# sheet1.net
KiCad netlist of a schematic drawn in Altium Designer
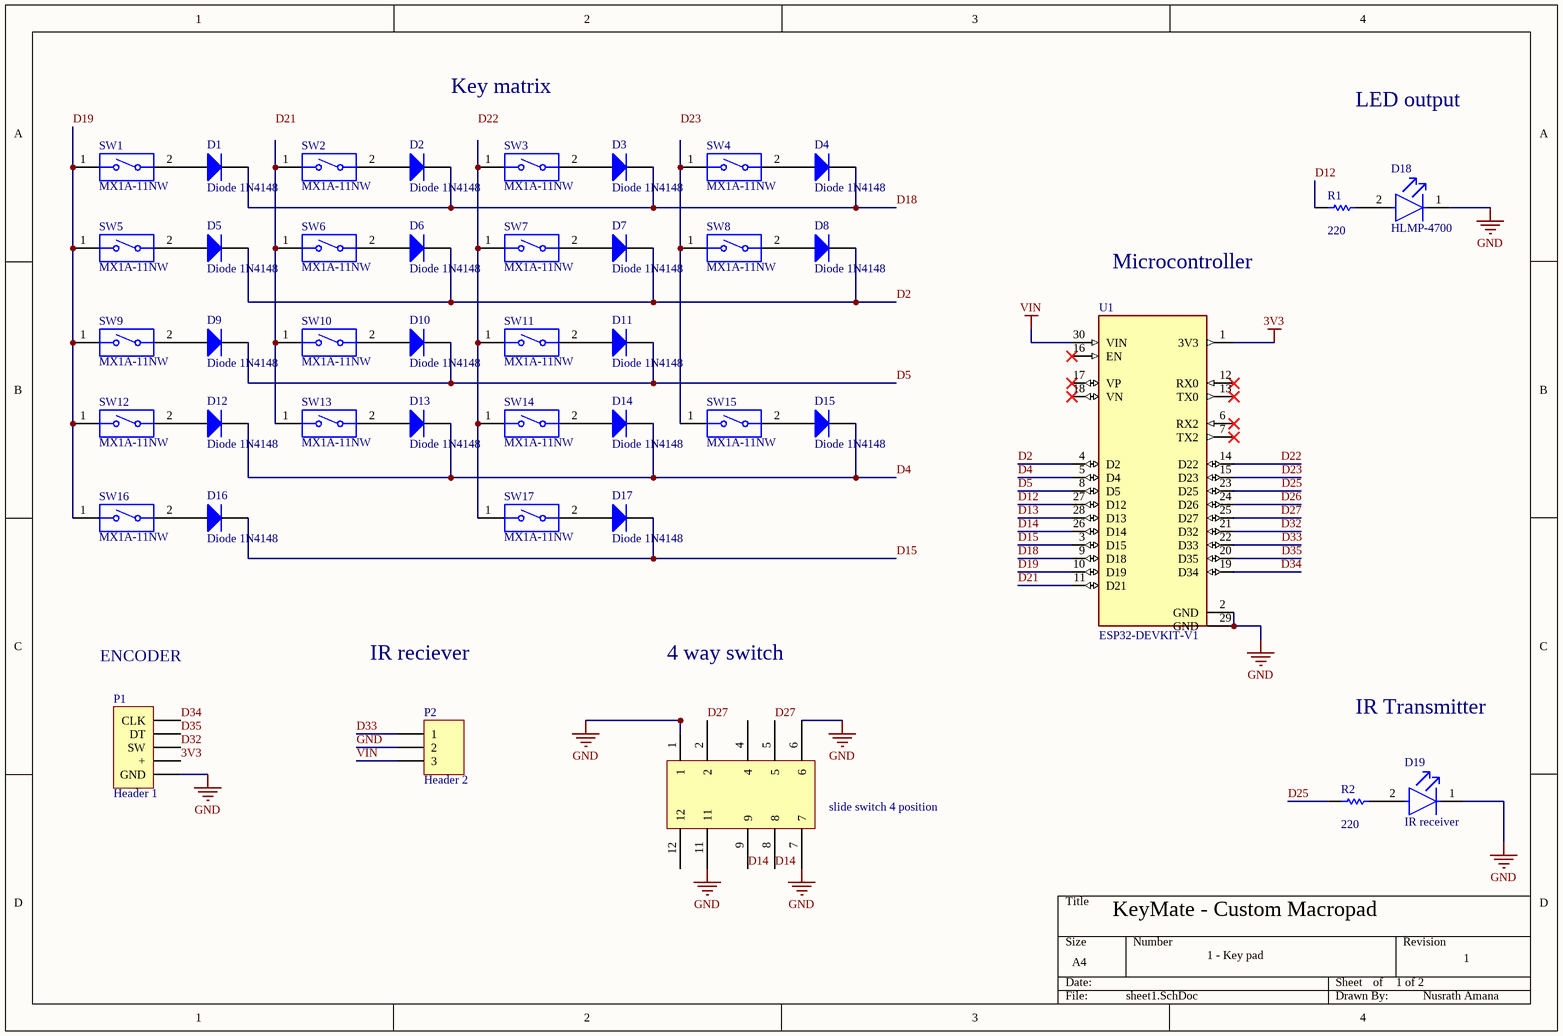
[diagram p0: sheet1.SchDoc]

(export (version "E")
  (design (tool "Eeschema 10.0.6"))
  (components
    (comp (ref "*1")
      (value "slide switch 4 position")
      (footprint "SWSLIDT_DP4T_S_20X8")
      (libsource (lib "switch") (part "slide switch 4 position"))
    )
    (comp (ref "D1")
      (value "Diode 1N4148")
      (footprint "DO-35")
      (description "High Conductance Fast Diode")
      (fields (field (name "PUBLISHER") "Altium Limited"))
      (libsource (lib "Miscellaneous Devices") (part "Diode 1N4148"))
    )
    (comp (ref "D2")
      (value "Diode 1N4148")
      (footprint "DO-35")
      (description "High Conductance Fast Diode")
      (fields (field (name "PUBLISHER") "Altium Limited"))
      (libsource (lib "Miscellaneous Devices") (part "Diode 1N4148"))
    )
    (comp (ref "D3")
      (value "Diode 1N4148")
      (footprint "DO-35")
      (description "High Conductance Fast Diode")
      (fields (field (name "PUBLISHER") "Altium Limited"))
      (libsource (lib "Miscellaneous Devices") (part "Diode 1N4148"))
    )
    (comp (ref "D4")
      (value "Diode 1N4148")
      (footprint "DO-35")
      (description "High Conductance Fast Diode")
      (fields (field (name "PUBLISHER") "Altium Limited"))
      (libsource (lib "Miscellaneous Devices") (part "Diode 1N4148"))
    )
    (comp (ref "D5")
      (value "Diode 1N4148")
      (footprint "DO-35")
      (description "High Conductance Fast Diode")
      (fields (field (name "PUBLISHER") "Altium Limited"))
      (libsource (lib "Miscellaneous Devices") (part "Diode 1N4148"))
    )
    (comp (ref "D6")
      (value "Diode 1N4148")
      (footprint "DO-35")
      (description "High Conductance Fast Diode")
      (fields (field (name "PUBLISHER") "Altium Limited"))
      (libsource (lib "Miscellaneous Devices") (part "Diode 1N4148"))
    )
    (comp (ref "D7")
      (value "Diode 1N4148")
      (footprint "DO-35")
      (description "High Conductance Fast Diode")
      (fields (field (name "PUBLISHER") "Altium Limited"))
      (libsource (lib "Miscellaneous Devices") (part "Diode 1N4148"))
    )
    (comp (ref "D8")
      (value "Diode 1N4148")
      (footprint "DO-35")
      (description "High Conductance Fast Diode")
      (fields (field (name "PUBLISHER") "Altium Limited"))
      (libsource (lib "Miscellaneous Devices") (part "Diode 1N4148"))
    )
    (comp (ref "D9")
      (value "Diode 1N4148")
      (footprint "DO-35")
      (description "High Conductance Fast Diode")
      (fields (field (name "PUBLISHER") "Altium Limited"))
      (libsource (lib "Miscellaneous Devices") (part "Diode 1N4148"))
    )
    (comp (ref "D10")
      (value "Diode 1N4148")
      (footprint "DO-35")
      (description "High Conductance Fast Diode")
      (fields (field (name "PUBLISHER") "Altium Limited"))
      (libsource (lib "Miscellaneous Devices") (part "Diode 1N4148"))
    )
    (comp (ref "D11")
      (value "Diode 1N4148")
      (footprint "DO-35")
      (description "High Conductance Fast Diode")
      (fields (field (name "PUBLISHER") "Altium Limited"))
      (libsource (lib "Miscellaneous Devices") (part "Diode 1N4148"))
    )
    (comp (ref "D12")
      (value "Diode 1N4148")
      (footprint "DO-35")
      (description "High Conductance Fast Diode")
      (fields (field (name "PUBLISHER") "Altium Limited"))
      (libsource (lib "Miscellaneous Devices") (part "Diode 1N4148"))
    )
    (comp (ref "D13")
      (value "Diode 1N4148")
      (footprint "DO-35")
      (description "High Conductance Fast Diode")
      (fields (field (name "PUBLISHER") "Altium Limited"))
      (libsource (lib "Miscellaneous Devices") (part "Diode 1N4148"))
    )
    (comp (ref "D14")
      (value "Diode 1N4148")
      (footprint "DO-35")
      (description "High Conductance Fast Diode")
      (fields (field (name "PUBLISHER") "Altium Limited"))
      (libsource (lib "Miscellaneous Devices") (part "Diode 1N4148"))
    )
    (comp (ref "D15")
      (value "Diode 1N4148")
      (footprint "DO-35")
      (description "High Conductance Fast Diode")
      (fields (field (name "PUBLISHER") "Altium Limited"))
      (libsource (lib "Miscellaneous Devices") (part "Diode 1N4148"))
    )
    (comp (ref "D16")
      (value "Diode 1N4148")
      (footprint "DO-35")
      (description "High Conductance Fast Diode")
      (fields (field (name "PUBLISHER") "Altium Limited"))
      (libsource (lib "Miscellaneous Devices") (part "Diode 1N4148"))
    )
    (comp (ref "D17")
      (value "Diode 1N4148")
      (footprint "DO-35")
      (description "High Conductance Fast Diode")
      (fields (field (name "PUBLISHER") "Altium Limited"))
      (libsource (lib "Miscellaneous Devices") (part "Diode 1N4148"))
    )
    (comp (ref "D18")
      (value "HLMP-4700")
      (footprint "FP-HLMP-4700-MFG")
      (description "LED RED DIFFUSED T-1 3/4 T/H")
      (fields
        (field (name "OCTOPART") "https://octopart.com/hlmp-4700-broadcom-71130526")
        (field (name "MANUFACTURER") "Broadcom")
      )
      (libsource (lib "Altium Content Vault") (part "8706943c75ba83719d021d2fdc84c58"))
    )
    (comp (ref "D19")
      (value "IR receiver")
      (footprint "FP-SFH_4550-MFG")
      (description "EMITTER IR 860NM 100MA RADIAL")
      (fields
        (field (name "MANUFACTURER PART NUMBER") "SFH 4550")
        (field (name "OCTOPART") "https://octopart.com/sfh+4550-osram+opto-55410894")
      )
      (libsource (lib "Altium Content Vault") (part "75a0115997dd6a71327e26aab64f6f8"))
    )
    (comp (ref "P1")
      (value "Header 1")
      (footprint "HDR1X5")
      (description "Header, 5-Pin")
      (fields (field (name "PUBLISHER") "Altium Limited"))
      (libsource (lib "Miscellaneous Connectors") (part "Header 5"))
    )
    (comp (ref "P2")
      (value "Header 2")
      (footprint "HDR1X3")
      (description "Header, 3-Pin")
      (fields (field (name "PUBLISHER") "Altium Limited"))
      (libsource (lib "Miscellaneous Connectors") (part "Header 3"))
    )
    (comp (ref "R1")
      (value "220")
      (footprint "AXIAL-0.3")
      (description "Resistor")
      (fields (field (name "Comment") "Res1") (field (name "PUBLISHER") "Altium Limited"))
      (libsource (lib "Miscellaneous Devices") (part "Res1"))
    )
    (comp (ref "R2")
      (value "220")
      (footprint "AXIAL-0.3")
      (description "Resistor")
      (fields (field (name "Comment") "Res1") (field (name "PUBLISHER") "Altium Limited"))
      (libsource (lib "Miscellaneous Devices") (part "Res1"))
    )
    (comp (ref "SW1")
      (value "MX1A-11NW")
      (footprint "CHRY-MX1A-11NW_V")
      (description "Keylock Switch, 12 V, -10 to 70 degC, 2-Pin THD, RoHS, Bulk")
      (fields (field (name "MANUFACTURER") "Cherry") (field (name "PART NO") "MX1A11NW"))
      (libsource (lib "Altium Content Vault") (part "KEYSW-SPST-2"))
    )
    (comp (ref "SW2")
      (value "MX1A-11NW")
      (footprint "CHRY-MX1A-11NW_V")
      (description "Keylock Switch, 12 V, -10 to 70 degC, 2-Pin THD, RoHS, Bulk")
      (fields (field (name "MANUFACTURER") "Cherry") (field (name "PART NO") "MX1A11NW"))
      (libsource (lib "Altium Content Vault") (part "KEYSW-SPST-2"))
    )
    (comp (ref "SW3")
      (value "MX1A-11NW")
      (footprint "CHRY-MX1A-11NW_V")
      (description "Keylock Switch, 12 V, -10 to 70 degC, 2-Pin THD, RoHS, Bulk")
      (fields (field (name "MANUFACTURER") "Cherry") (field (name "PART NO") "MX1A11NW"))
      (libsource (lib "Altium Content Vault") (part "KEYSW-SPST-2"))
    )
    (comp (ref "SW4")
      (value "MX1A-11NW")
      (footprint "CHRY-MX1A-11NW_V")
      (description "Keylock Switch, 12 V, -10 to 70 degC, 2-Pin THD, RoHS, Bulk")
      (fields (field (name "MANUFACTURER") "Cherry") (field (name "PART NO") "MX1A11NW"))
      (libsource (lib "Altium Content Vault") (part "KEYSW-SPST-2"))
    )
    (comp (ref "SW5")
      (value "MX1A-11NW")
      (footprint "CHRY-MX1A-11NW_V")
      (description "Keylock Switch, 12 V, -10 to 70 degC, 2-Pin THD, RoHS, Bulk")
      (fields (field (name "MANUFACTURER") "Cherry") (field (name "PART NO") "MX1A11NW"))
      (libsource (lib "Altium Content Vault") (part "KEYSW-SPST-2"))
    )
    (comp (ref "SW6")
      (value "MX1A-11NW")
      (footprint "CHRY-MX1A-11NW_V")
      (description "Keylock Switch, 12 V, -10 to 70 degC, 2-Pin THD, RoHS, Bulk")
      (fields (field (name "MANUFACTURER") "Cherry") (field (name "PART NO") "MX1A11NW"))
      (libsource (lib "Altium Content Vault") (part "KEYSW-SPST-2"))
    )
    (comp (ref "SW7")
      (value "MX1A-11NW")
      (footprint "CHRY-MX1A-11NW_V")
      (description "Keylock Switch, 12 V, -10 to 70 degC, 2-Pin THD, RoHS, Bulk")
      (fields (field (name "MANUFACTURER") "Cherry") (field (name "PART NO") "MX1A11NW"))
      (libsource (lib "Altium Content Vault") (part "KEYSW-SPST-2"))
    )
    (comp (ref "SW8")
      (value "MX1A-11NW")
      (footprint "CHRY-MX1A-11NW_V")
      (description "Keylock Switch, 12 V, -10 to 70 degC, 2-Pin THD, RoHS, Bulk")
      (fields (field (name "MANUFACTURER") "Cherry") (field (name "PART NO") "MX1A11NW"))
      (libsource (lib "Altium Content Vault") (part "KEYSW-SPST-2"))
    )
    (comp (ref "SW9")
      (value "MX1A-11NW")
      (footprint "CHRY-MX1A-11NW_V")
      (description "Keylock Switch, 12 V, -10 to 70 degC, 2-Pin THD, RoHS, Bulk")
      (fields (field (name "MANUFACTURER") "Cherry") (field (name "PART NO") "MX1A11NW"))
      (libsource (lib "Altium Content Vault") (part "KEYSW-SPST-2"))
    )
    (comp (ref "SW10")
      (value "MX1A-11NW")
      (footprint "CHRY-MX1A-11NW_V")
      (description "Keylock Switch, 12 V, -10 to 70 degC, 2-Pin THD, RoHS, Bulk")
      (fields (field (name "MANUFACTURER") "Cherry") (field (name "PART NO") "MX1A11NW"))
      (libsource (lib "Altium Content Vault") (part "KEYSW-SPST-2"))
    )
    (comp (ref "SW11")
      (value "MX1A-11NW")
      (footprint "CHRY-MX1A-11NW_V")
      (description "Keylock Switch, 12 V, -10 to 70 degC, 2-Pin THD, RoHS, Bulk")
      (fields (field (name "MANUFACTURER") "Cherry") (field (name "PART NO") "MX1A11NW"))
      (libsource (lib "Altium Content Vault") (part "KEYSW-SPST-2"))
    )
    (comp (ref "SW12")
      (value "MX1A-11NW")
      (footprint "CHRY-MX1A-11NW_V")
      (description "Keylock Switch, 12 V, -10 to 70 degC, 2-Pin THD, RoHS, Bulk")
      (fields (field (name "MANUFACTURER") "Cherry") (field (name "PART NO") "MX1A11NW"))
      (libsource (lib "Altium Content Vault") (part "KEYSW-SPST-2"))
    )
    (comp (ref "SW13")
      (value "MX1A-11NW")
      (footprint "CHRY-MX1A-11NW_V")
      (description "Keylock Switch, 12 V, -10 to 70 degC, 2-Pin THD, RoHS, Bulk")
      (fields (field (name "MANUFACTURER") "Cherry") (field (name "PART NO") "MX1A11NW"))
      (libsource (lib "Altium Content Vault") (part "KEYSW-SPST-2"))
    )
    (comp (ref "SW14")
      (value "MX1A-11NW")
      (footprint "CHRY-MX1A-11NW_V")
      (description "Keylock Switch, 12 V, -10 to 70 degC, 2-Pin THD, RoHS, Bulk")
      (fields (field (name "MANUFACTURER") "Cherry") (field (name "PART NO") "MX1A11NW"))
      (libsource (lib "Altium Content Vault") (part "KEYSW-SPST-2"))
    )
    (comp (ref "SW15")
      (value "MX1A-11NW")
      (footprint "CHRY-MX1A-11NW_V")
      (description "Keylock Switch, 12 V, -10 to 70 degC, 2-Pin THD, RoHS, Bulk")
      (fields (field (name "MANUFACTURER") "Cherry") (field (name "PART NO") "MX1A11NW"))
      (libsource (lib "Altium Content Vault") (part "KEYSW-SPST-2"))
    )
    (comp (ref "SW16")
      (value "MX1A-11NW")
      (footprint "CHRY-MX1A-11NW_V")
      (description "Keylock Switch, 12 V, -10 to 70 degC, 2-Pin THD, RoHS, Bulk")
      (fields (field (name "MANUFACTURER") "Cherry") (field (name "PART NO") "MX1A11NW"))
      (libsource (lib "Altium Content Vault") (part "KEYSW-SPST-2"))
    )
    (comp (ref "SW17")
      (value "MX1A-11NW")
      (footprint "CHRY-MX1A-11NW_V")
      (description "Keylock Switch, 12 V, -10 to 70 degC, 2-Pin THD, RoHS, Bulk")
      (fields (field (name "MANUFACTURER") "Cherry") (field (name "PART NO") "MX1A11NW"))
      (libsource (lib "Altium Content Vault") (part "KEYSW-SPST-2"))
    )
    (comp (ref "U1")
      (value "ESP32-DEVKIT-V1")
      (footprint "MODULE_ESP32_DEVKIT_V1")
      (fields (field (name "MF") "Do it"))
      (libsource (lib "ESP32-DEVKIT-V1 -modified") (part "ESP32-DEVKIT-V1"))
    )
  )
  (nets
    (net (code "1") (name "/D2") (class "Default")
      (node (ref "D5") (pin "2") (pinfunction "K_2") (pintype "passive"))
      (node (ref "D6") (pin "2") (pinfunction "K_2") (pintype "passive"))
      (node (ref "D7") (pin "2") (pinfunction "K_2") (pintype "passive"))
      (node (ref "D8") (pin "2") (pinfunction "K_2") (pintype "passive"))
      (node (ref "U1") (pin "4") (pinfunction "D2_4") (pintype "bidirectional"))
    )
    (net (code "2") (name "/D4") (class "Default")
      (node (ref "D12") (pin "2") (pinfunction "K_2") (pintype "passive"))
      (node (ref "D13") (pin "2") (pinfunction "K_2") (pintype "passive"))
      (node (ref "D14") (pin "2") (pinfunction "K_2") (pintype "passive"))
      (node (ref "D15") (pin "2") (pinfunction "K_2") (pintype "passive"))
      (node (ref "U1") (pin "5") (pinfunction "D4_5") (pintype "bidirectional"))
    )
    (net (code "3") (name "/D5") (class "Default")
      (node (ref "D10") (pin "2") (pinfunction "K_2") (pintype "passive"))
      (node (ref "D11") (pin "2") (pinfunction "K_2") (pintype "passive"))
      (node (ref "D9") (pin "2") (pinfunction "K_2") (pintype "passive"))
      (node (ref "U1") (pin "8") (pinfunction "D5_8") (pintype "bidirectional"))
    )
    (net (code "4") (name "/D12") (class "Default")
      (node (ref "R1") (pin "1") (pinfunction "1_1") (pintype "passive"))
      (node (ref "U1") (pin "27") (pinfunction "D12_27") (pintype "bidirectional"))
    )
    (net (code "5") (name "/D13") (class "Default")
      (node (ref "U1") (pin "28") (pinfunction "D13_28") (pintype "bidirectional"))
    )
    (net (code "6") (name "/D14") (class "Default")
      (node (ref "*1") (pin "8") (pinfunction "8_8") (pintype "passive"))
      (node (ref "*1") (pin "9") (pinfunction "9_9") (pintype "passive"))
      (node (ref "U1") (pin "26") (pinfunction "D14_26") (pintype "bidirectional"))
    )
    (net (code "7") (name "/D15") (class "Default")
      (node (ref "D16") (pin "2") (pinfunction "K_2") (pintype "passive"))
      (node (ref "D17") (pin "2") (pinfunction "K_2") (pintype "passive"))
      (node (ref "U1") (pin "3") (pinfunction "D15_3") (pintype "bidirectional"))
    )
    (net (code "8") (name "/D18") (class "Default")
      (node (ref "D1") (pin "2") (pinfunction "K_2") (pintype "passive"))
      (node (ref "D2") (pin "2") (pinfunction "K_2") (pintype "passive"))
      (node (ref "D3") (pin "2") (pinfunction "K_2") (pintype "passive"))
      (node (ref "D4") (pin "2") (pinfunction "K_2") (pintype "passive"))
      (node (ref "U1") (pin "9") (pinfunction "D18_9") (pintype "bidirectional"))
    )
    (net (code "9") (name "/D19") (class "Default")
      (node (ref "SW1") (pin "1") (pinfunction "1_1") (pintype "passive"))
      (node (ref "SW12") (pin "1") (pinfunction "1_1") (pintype "passive"))
      (node (ref "SW16") (pin "1") (pinfunction "1_1") (pintype "passive"))
      (node (ref "SW5") (pin "1") (pinfunction "1_1") (pintype "passive"))
      (node (ref "SW9") (pin "1") (pinfunction "1_1") (pintype "passive"))
      (node (ref "U1") (pin "10") (pinfunction "D19_10") (pintype "bidirectional"))
    )
    (net (code "10") (name "/D21") (class "Default")
      (node (ref "U1") (pin "11") (pinfunction "D21_11") (pintype "bidirectional"))
    )
    (net (code "11") (name "/D22") (class "Default")
      (node (ref "U1") (pin "14") (pinfunction "D22_14") (pintype "bidirectional"))
    )
    (net (code "12") (name "/D23") (class "Default")
      (node (ref "U1") (pin "15") (pinfunction "D23_15") (pintype "bidirectional"))
    )
    (net (code "13") (name "/D25") (class "Default")
      (node (ref "R2") (pin "1") (pinfunction "1_1") (pintype "passive"))
      (node (ref "U1") (pin "23") (pinfunction "D25_23") (pintype "bidirectional"))
    )
    (net (code "14") (name "/D26") (class "Default")
      (node (ref "U1") (pin "24") (pinfunction "D26_24") (pintype "bidirectional"))
    )
    (net (code "15") (name "/D27") (class "Default")
      (node (ref "*1") (pin "2") (pinfunction "2_2") (pintype "passive"))
      (node (ref "*1") (pin "5") (pinfunction "5_5") (pintype "passive"))
      (node (ref "U1") (pin "25") (pinfunction "D27_25") (pintype "bidirectional"))
    )
    (net (code "16") (name "/D32") (class "Default")
      (node (ref "P1") (pin "3") (pinfunction "SW_3") (pintype "passive"))
      (node (ref "U1") (pin "21") (pinfunction "D32_21") (pintype "bidirectional"))
    )
    (net (code "17") (name "/D33") (class "Default")
      (node (ref "P2") (pin "1") (pinfunction "1_1") (pintype "passive"))
      (node (ref "U1") (pin "22") (pinfunction "D33_22") (pintype "bidirectional"))
    )
    (net (code "18") (name "/D34") (class "Default")
      (node (ref "P1") (pin "5") (pinfunction "CLK_5") (pintype "passive"))
      (node (ref "U1") (pin "19") (pinfunction "D34_19") (pintype "bidirectional"))
    )
    (net (code "19") (name "/D35") (class "Default")
      (node (ref "P1") (pin "4") (pinfunction "DT_4") (pintype "passive"))
      (node (ref "U1") (pin "20") (pinfunction "D35_20") (pintype "bidirectional"))
    )
    (net (code "20") (name "3V3") (class "Default")
      (node (ref "P1") (pin "2") (pinfunction "+_2") (pintype "passive"))
      (node (ref "U1") (pin "1") (pinfunction "3V3_1") (pintype "output"))
    )
    (net (code "21") (name "GND") (class "Default")
      (node (ref "*1") (pin "1") (pinfunction "1_1") (pintype "passive"))
      (node (ref "*1") (pin "11") (pinfunction "11_11") (pintype "passive"))
      (node (ref "*1") (pin "6") (pinfunction "6_6") (pintype "passive"))
      (node (ref "*1") (pin "7") (pinfunction "7_7") (pintype "passive"))
      (node (ref "D18") (pin "1") (pinfunction "C_1") (pintype "passive"))
      (node (ref "D19") (pin "1") (pinfunction "C_1") (pintype "passive"))
      (node (ref "P1") (pin "1") (pinfunction "GND_1") (pintype "passive"))
      (node (ref "P2") (pin "2") (pinfunction "2_2") (pintype "passive"))
      (node (ref "U1") (pin "2") (pinfunction "GND_2") (pintype "power_in"))
      (node (ref "U1") (pin "29") (pinfunction "GND_29") (pintype "power_in"))
    )
    (net (code "22") (name "Net-(D1-A)") (class "Default")
      (node (ref "D1") (pin "1") (pinfunction "A_1") (pintype "passive"))
      (node (ref "SW1") (pin "2") (pinfunction "2_2") (pintype "passive"))
    )
    (net (code "23") (name "Net-(D2-A)") (class "Default")
      (node (ref "D2") (pin "1") (pinfunction "A_1") (pintype "passive"))
      (node (ref "SW2") (pin "2") (pinfunction "2_2") (pintype "passive"))
    )
    (net (code "24") (name "Net-(D3-A)") (class "Default")
      (node (ref "D3") (pin "1") (pinfunction "A_1") (pintype "passive"))
      (node (ref "SW3") (pin "2") (pinfunction "2_2") (pintype "passive"))
    )
    (net (code "25") (name "Net-(D4-A)") (class "Default")
      (node (ref "D4") (pin "1") (pinfunction "A_1") (pintype "passive"))
      (node (ref "SW4") (pin "2") (pinfunction "2_2") (pintype "passive"))
    )
    (net (code "26") (name "Net-(D5-A)") (class "Default")
      (node (ref "D5") (pin "1") (pinfunction "A_1") (pintype "passive"))
      (node (ref "SW5") (pin "2") (pinfunction "2_2") (pintype "passive"))
    )
    (net (code "27") (name "Net-(D6-A)") (class "Default")
      (node (ref "D6") (pin "1") (pinfunction "A_1") (pintype "passive"))
      (node (ref "SW6") (pin "2") (pinfunction "2_2") (pintype "passive"))
    )
    (net (code "28") (name "Net-(D7-A)") (class "Default")
      (node (ref "D7") (pin "1") (pinfunction "A_1") (pintype "passive"))
      (node (ref "SW7") (pin "2") (pinfunction "2_2") (pintype "passive"))
    )
    (net (code "29") (name "Net-(D8-A)") (class "Default")
      (node (ref "D8") (pin "1") (pinfunction "A_1") (pintype "passive"))
      (node (ref "SW8") (pin "2") (pinfunction "2_2") (pintype "passive"))
    )
    (net (code "30") (name "Net-(D9-A)") (class "Default")
      (node (ref "D9") (pin "1") (pinfunction "A_1") (pintype "passive"))
      (node (ref "SW9") (pin "2") (pinfunction "2_2") (pintype "passive"))
    )
    (net (code "31") (name "Net-(D10-A)") (class "Default")
      (node (ref "D10") (pin "1") (pinfunction "A_1") (pintype "passive"))
      (node (ref "SW10") (pin "2") (pinfunction "2_2") (pintype "passive"))
    )
    (net (code "32") (name "Net-(D11-A)") (class "Default")
      (node (ref "D11") (pin "1") (pinfunction "A_1") (pintype "passive"))
      (node (ref "SW11") (pin "2") (pinfunction "2_2") (pintype "passive"))
    )
    (net (code "33") (name "Net-(D12-A)") (class "Default")
      (node (ref "D12") (pin "1") (pinfunction "A_1") (pintype "passive"))
      (node (ref "SW12") (pin "2") (pinfunction "2_2") (pintype "passive"))
    )
    (net (code "34") (name "Net-(D13-A)") (class "Default")
      (node (ref "D13") (pin "1") (pinfunction "A_1") (pintype "passive"))
      (node (ref "SW13") (pin "2") (pinfunction "2_2") (pintype "passive"))
    )
    (net (code "35") (name "Net-(D14-A)") (class "Default")
      (node (ref "D14") (pin "1") (pinfunction "A_1") (pintype "passive"))
      (node (ref "SW14") (pin "2") (pinfunction "2_2") (pintype "passive"))
    )
    (net (code "36") (name "Net-(D15-A)") (class "Default")
      (node (ref "D15") (pin "1") (pinfunction "A_1") (pintype "passive"))
      (node (ref "SW15") (pin "2") (pinfunction "2_2") (pintype "passive"))
    )
    (net (code "37") (name "Net-(D16-A)") (class "Default")
      (node (ref "D16") (pin "1") (pinfunction "A_1") (pintype "passive"))
      (node (ref "SW16") (pin "2") (pinfunction "2_2") (pintype "passive"))
    )
    (net (code "38") (name "Net-(D17-A)") (class "Default")
      (node (ref "D17") (pin "1") (pinfunction "A_1") (pintype "passive"))
      (node (ref "SW17") (pin "2") (pinfunction "2_2") (pintype "passive"))
    )
    (net (code "39") (name "Net-(D18-A)") (class "Default")
      (node (ref "D18") (pin "2") (pinfunction "A_2") (pintype "passive"))
      (node (ref "R1") (pin "2") (pinfunction "2_2") (pintype "passive"))
    )
    (net (code "40") (name "Net-(D19-A)") (class "Default")
      (node (ref "D19") (pin "2") (pinfunction "A_2") (pintype "passive"))
      (node (ref "R2") (pin "2") (pinfunction "2_2") (pintype "passive"))
    )
    (net (code "41") (name "Net-(SW10-Pad1)") (class "Default")
      (node (ref "SW10") (pin "1") (pinfunction "1_1") (pintype "passive"))
      (node (ref "SW13") (pin "1") (pinfunction "1_1") (pintype "passive"))
      (node (ref "SW2") (pin "1") (pinfunction "1_1") (pintype "passive"))
      (node (ref "SW6") (pin "1") (pinfunction "1_1") (pintype "passive"))
    )
    (net (code "42") (name "Net-(SW11-Pad1)") (class "Default")
      (node (ref "SW11") (pin "1") (pinfunction "1_1") (pintype "passive"))
      (node (ref "SW14") (pin "1") (pinfunction "1_1") (pintype "passive"))
      (node (ref "SW17") (pin "1") (pinfunction "1_1") (pintype "passive"))
      (node (ref "SW3") (pin "1") (pinfunction "1_1") (pintype "passive"))
      (node (ref "SW7") (pin "1") (pinfunction "1_1") (pintype "passive"))
    )
    (net (code "43") (name "Net-(SW15-Pad1)") (class "Default")
      (node (ref "SW15") (pin "1") (pinfunction "1_1") (pintype "passive"))
      (node (ref "SW4") (pin "1") (pinfunction "1_1") (pintype "passive"))
      (node (ref "SW8") (pin "1") (pinfunction "1_1") (pintype "passive"))
    )
    (net (code "44") (name "VIN") (class "Default")
      (node (ref "P2") (pin "3") (pinfunction "3_3") (pintype "passive"))
      (node (ref "U1") (pin "30") (pinfunction "VIN_30") (pintype "input"))
    )
    (net (code "45") (name "unconnected-(*1-Pad4)") (class "Default")
      (node (ref "*1") (pin "4") (pinfunction "4_4") (pintype "passive"))
    )
    (net (code "46") (name "unconnected-(*1-Pad12)") (class "Default")
      (node (ref "*1") (pin "12") (pinfunction "12_12") (pintype "passive"))
    )
    (net (code "47") (name "unconnected-(U1-EN-Pad16)") (class "Default")
      (node (ref "U1") (pin "16") (pinfunction "EN_16") (pintype "input+no_connect"))
    )
    (net (code "48") (name "unconnected-(U1-RX0-Pad12)") (class "Default")
      (node (ref "U1") (pin "12") (pinfunction "RX0_12") (pintype "input+no_connect"))
    )
    (net (code "49") (name "unconnected-(U1-RX2-Pad6)") (class "Default")
      (node (ref "U1") (pin "6") (pinfunction "RX2_6") (pintype "input+no_connect"))
    )
    (net (code "50") (name "unconnected-(U1-TX0-Pad13)") (class "Default")
      (node (ref "U1") (pin "13") (pinfunction "TX0_13") (pintype "output+no_connect"))
    )
    (net (code "51") (name "unconnected-(U1-TX2-Pad7)") (class "Default")
      (node (ref "U1") (pin "7") (pinfunction "TX2_7") (pintype "output+no_connect"))
    )
    (net (code "52") (name "unconnected-(U1-VN-Pad18)") (class "Default")
      (node (ref "U1") (pin "18") (pinfunction "VN_18") (pintype "bidirectional+no_connect"))
    )
    (net (code "53") (name "unconnected-(U1-VP-Pad17)") (class "Default")
      (node (ref "U1") (pin "17") (pinfunction "VP_17") (pintype "bidirectional+no_connect"))
    )
  )
)
